# 07_Power_Supply_AC_to_DC.net
KiCad netlist of a schematic drawn in Altium Designer
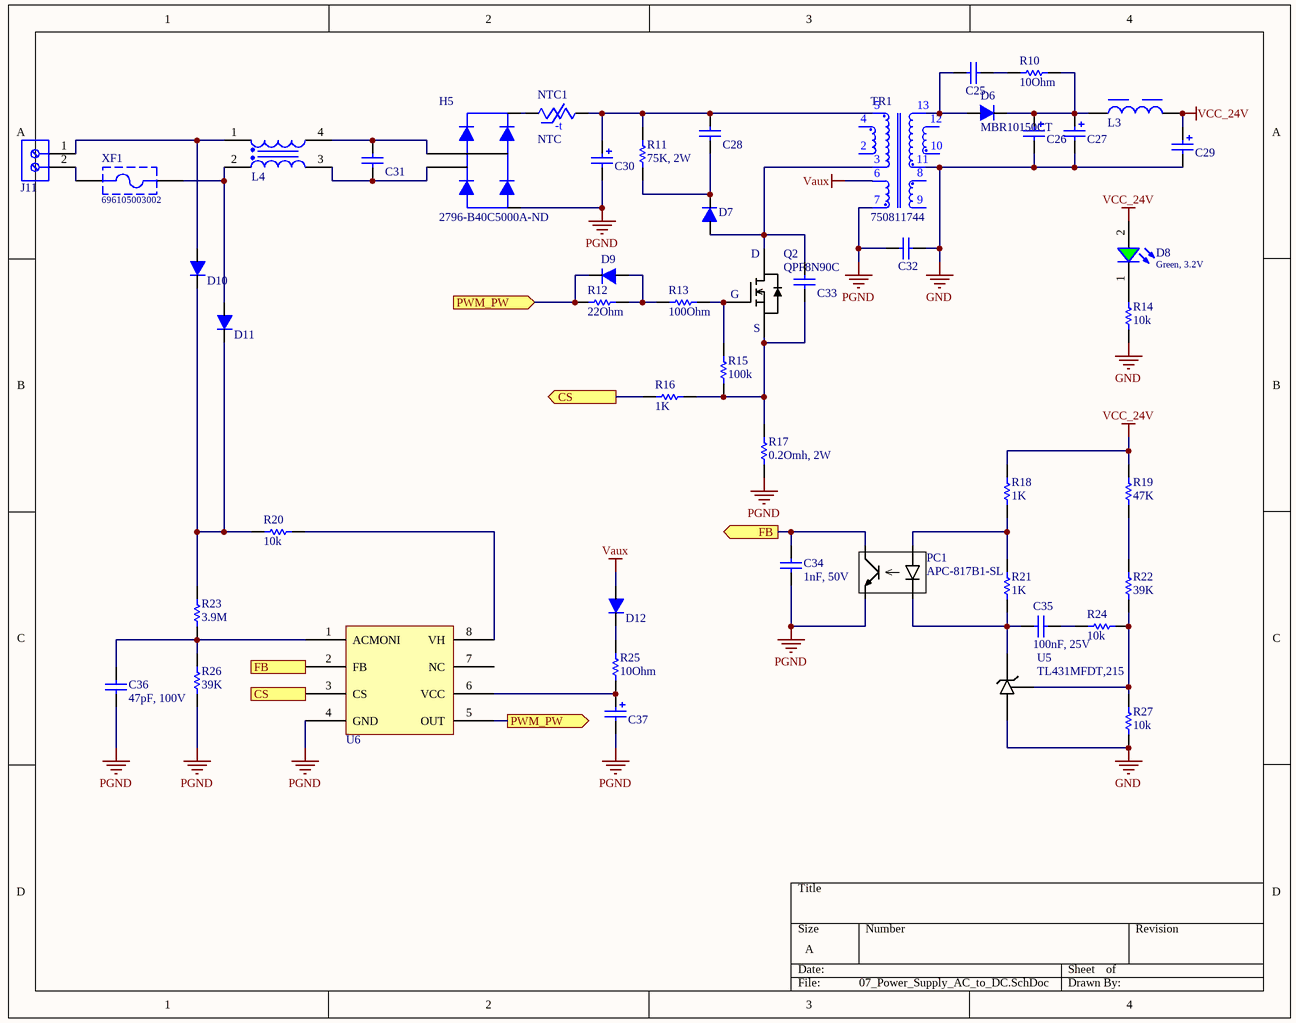
[diagram p0: 07_Power_Supply_AC_to_DC.SchDoc]

(export (version "E")
  (design (tool "Eeschema 10.0.6"))
  (components
    (comp (ref "C25")
      (value "1nF")
      (footprint "WCAP-CSMH_0805_L2W1.25H0.8_Reflow")
      (fields
        (field (name "MANUFACTURER PART NUMBER") "885342207013")
        (field (name "MANUFACTURER") "Wurth Elektronik")
      )
      (libsource (lib "Altium_WCAP-CSMH (rev22c)") (part "885342207013"))
    )
    (comp (ref "C26")
      (value "1200uF")
      (footprint "WCAP-ATG8_D16H31.5")
      (description "WCAP-ATG8 Aluminum Electrolytic Capacitor, Radial THT, D16xH31.5mm, 1200uF, 63V")
      (fields
        (field (name "MANUFACTURER") "Wurth Elektronik")
        (field (name "MANUFACTURER PART NUMBER") "860010780025")
      )
      (libsource (lib "Altium_WCAP-ATG8 (rev22a)") (part "860010780025"))
    )
    (comp (ref "C27")
      (value "1200uF")
      (footprint "WCAP-ATG8_D16H31.5")
      (description "WCAP-ATG8 Aluminum Electrolytic Capacitor, Radial THT, D16xH31.5mm, 1200uF, 63V")
      (fields
        (field (name "MANUFACTURER") "Wurth Elektronik")
        (field (name "MANUFACTURER PART NUMBER") "860010780025")
      )
      (libsource (lib "Altium_WCAP-ATG8 (rev22a)") (part "860010780025"))
    )
    (comp (ref "C28")
      (value "4.7nF")
      (footprint "WCAP-CSMH_1206_L3.2W1.6H1.25")
      (fields
        (field (name "MANUFACTURER PART NUMBER") "885342208008")
        (field (name "MANUFACTURER") "Wurth Elektronik")
      )
      (libsource (lib "Altium_WCAP-CSMH (rev22c)") (part "885342208008"))
    )
    (comp (ref "C29")
      (value "100uF")
      (footprint "WCAP-ATG8_D8H11.5")
      (description "WCAP-ATG8 Aluminum Electrolytic Capacitor, Radial THT, D8xH11.5mm, 100uF, 50V")
      (fields
        (field (name "MANUFACTURER") "Wurth Elektronik")
        (field (name "MANUFACTURER PART NUMBER") "860010674014")
      )
      (libsource (lib "Altium_WCAP-ATG8 (rev22a)") (part "860010674014"))
    )
    (comp (ref "C30")
      (value "220uF")
      (footprint "WCAP-AI3H_D22H50")
      (description "WCAP-AI3H Aluminum Electrolytic Capacitor, Snap-In, D22xH50mm, 220uF, 450V")
      (fields
        (field (name "MANUFACTURER") "Wurth Elektronik")
        (field (name "MANUFACTURER PART NUMBER") "861141483007")
      )
      (libsource (lib "Altium_WCAP-AI3H (rev22a)") (part "861141483007"))
    )
    (comp (ref "C31")
      (value "2.2uF")
      (footprint "WCAP-FTX2_L26W15H25")
      (description "WCAP-FTX2 Film Capacitor, THT, L26W15H25mm, 2.2uF, 275VAC")
      (fields
        (field (name "MANUFACTURER") "Wurth Elektronik")
        (field (name "MANUFACTURER PART NUMBER") "890324026034")
      )
      (libsource (lib "Altium_WCAP-FTX2 (rev22a)") (part "890324026034"))
    )
    (comp (ref "C32")
      (value "2.2nF")
      (footprint "WCAP-CSSA_2211_L5.7W2.8H2.5")
      (description "WCAP-CSSA Multilayer Ceramic Chip Safety Capacitor, 2211, X7R Class II, X1/Y2, 2.2nF, 250VAC")
      (fields
        (field (name "MANUFACTURER") "Wurth Elektronik")
        (field (name "MANUFACTURER PART NUMBER") "8853522130151")
      )
      (libsource (lib "Altium_WCAP-CSSA (rev22a)") (part "8853522130151"))
    )
    (comp (ref "C33")
      (value "22pF")
      (footprint "WCAP-CSMH_1210_L3.2W2.5H0.95")
      (fields
        (field (name "MANUFACTURER PART NUMBER") "885342009002")
        (field (name "MANUFACTURER") "Wurth Elektronik")
      )
      (libsource (lib "Altium_WCAP-CSMH (rev22c)") (part "885342009002"))
    )
    (comp (ref "C34")
      (value "1nF, 50V")
      (footprint "WCAP-CSGP_0805_H=0.8mm_Reflow")
      (description "WCAP-CSGP Multilayer Ceramic Chip Capacitor, General Purpose, size 0805, NP0, 1nF, 50V")
      (fields
        (field (name "MANUFACTURER PART NUMBER") "885012007063")
        (field (name "MANUFACTURER") "Wurth Elektronik")
      )
      (libsource (lib "Altium_WCAP-CSGP (rev20a)") (part "885012007063"))
    )
    (comp (ref "C35")
      (value "100nF, 25V")
      (footprint "WCAP-CSGP_0805_H=0.8mm_Reflow")
      (description "WCAP-CSGP Multilayer Ceramic Chip Capacitor, General Purpose, size 0805, X7R, 100nF, 25V")
      (fields
        (field (name "MANUFACTURER PART NUMBER") "885012207072")
        (field (name "MANUFACTURER") "Wurth Elektronik")
      )
      (libsource (lib "Altium_WCAP-CSGP (rev20a)") (part "885012207072"))
    )
    (comp (ref "C36")
      (value "47pF, 100V")
      (footprint "WCAP-CSGP_0805_H=0.6mm_Reflow")
      (description "WCAP-CSGP Multilayer Ceramic Chip Capacitor, General Purpose, size 0805, NP0, 47pF, 100V")
      (fields
        (field (name "MANUFACTURER PART NUMBER") "885012007080")
        (field (name "MANUFACTURER") "Wurth Elektronik")
      )
      (libsource (lib "Altium_WCAP-CSGP (rev20a)") (part "885012007080"))
    )
    (comp (ref "C37")
      (value "10uF")
      (footprint "WCAP-ATG8_D5H11")
      (description "WCAP-ATG8 Aluminum Electrolytic Capacitor, Radial THT, D5xH11mm, 10uF, 50V")
      (fields
        (field (name "MANUFACTURER") "Wurth Elektronik")
        (field (name "MANUFACTURER PART NUMBER") "860010672009")
      )
      (libsource (lib "Altium_WCAP-ATG8 (rev22a)") (part "860010672009"))
    )
    (comp (ref "D6")
      (value "MBR10150CT")
      (footprint "MBR10150CT")
      (description "DIODE ARRAY SCHOTTKY 150V TO220")
      (fields (field (name "MFR") "SMC Diode Solutions"))
      (libsource (lib "YenDoo") (part "Diode"))
    )
    (comp (ref "D7")
      (value "RS1M-13-F")
      (footprint "SMA")
      (description "DIODE GEN PURP 1KV 1A SMA")
      (fields (field (name "MFR") "Diodes Incorporated"))
      (libsource (lib "YenDoo") (part "Diode"))
    )
    (comp (ref "D8")
      (value "Green, 3.2V")
      (footprint "WL-SMCW_0603_H=0.7mm")
      (description "WL-SMCW SMT Mono-color Chip LED Waterclear, size 0603, Green, 3.2V, 140deg")
      (fields (field (name "PART NUMBER") "150060GS75000") (field (name "PUBLISHER") "Wurth Elektronik"))
      (libsource (lib "Altium_WL-SMCW (rev20a)") (part "150060GS75000"))
    )
    (comp (ref "D9")
      (value "CDBA360-HF")
      (footprint "SMA")
      (description "DIODE SCHOTTKY 60V 3A DO214AC")
      (fields (field (name "MFR") "Comchip Technology"))
      (libsource (lib "YenDoo") (part "Diode"))
    )
    (comp (ref "D10")
      (value "RFU02VSM8STR")
      (footprint "Flat Lead")
      (description "DIODE GP 800V 200MA TUMD2SM")
      (fields (field (name "MFR") "Rohm Semiconductor"))
      (libsource (lib "YenDoo") (part "Diode"))
    )
    (comp (ref "D11")
      (value "RFU02VSM8STR")
      (footprint "Flat Lead")
      (description "DIODE GP 800V 200MA TUMD2SM")
      (fields (field (name "MFR") "Rohm Semiconductor"))
      (libsource (lib "YenDoo") (part "Diode"))
    )
    (comp (ref "D12")
      (value "RS1M-13-F")
      (footprint "SMA")
      (description "DIODE GEN PURP 1KV 1A SMA")
      (fields (field (name "MFR") "Diodes Incorporated"))
      (libsource (lib "YenDoo") (part "Diode"))
    )
    (comp (ref "H5")
      (value "2796-B40C5000A-ND")
      (footprint "GBJ-4")
      (description "Bridge Rectifier Single Phase Standard 80 V Through Hole 4-SIP")
      (libsource (lib "YenDoo") (part "H Bridge"))
    )
    (comp (ref "J11")
      (value "691137710002")
      (footprint "691137710002")
      (description "WR-TBL Series 1377 Horizontal Entry, Through Hole, pitch 5mm, 2p")
      (fields (field (name "MANUFACTURER") "Wurth Elektronik"))
      (libsource (lib "Altium_WR-TBL (rev22a)") (part "691137710002"))
    )
    (comp (ref "L3")
      (value "10µH, 7A")
      (footprint "WE-LHMI_1040")
      (description "WE-LHMI SMT Power Inductor, size 1040, 10µH, 7A, 30mΩ")
      (fields
        (field (name "MANUFACTURER PART NUMBER") "74437368100")
        (field (name "MANUFACTURER") "Wurth Elektronik")
      )
      (libsource (lib "WE-LHMI (rev22a)") (part "74437368100"))
    )
    (comp (ref "L4")
      (value "13mH")
      (footprint "WE-FC_UT20V")
      (description "WE-FC THT Common Mode Power Line Choke, UT20V, 13mH, 0.8A, 0.708Ω")
      (fields
        (field (name "MANUFACTURER PART NUMBER") "7448640415")
        (field (name "MANUFACTURER") "Wurth Elektronik")
      )
      (libsource (lib "WE-FC (rev22a)") (part "7448640415"))
    )
    (comp (ref "NTC1")
      (value "NTC")
      (footprint "NTC")
      (description "THERMISTOR NTC 15OHM 3000K")
      (fields (field (name "MFR") "EPCOS - TDK Electronics") (field (name "TOLERANCE") "±20%"))
      (libsource (lib "YenDoo") (part "NTC"))
    )
    (comp (ref "PC1")
      (value "APC-817B1-SL")
      (footprint "APC-817B1-SL")
      (description "DIP4, DC INPUT, PHOTO TRANSISTOR")
      (fields (field (name "MFR") "American Bright Optoelectronics Corporation"))
      (libsource (lib "YenDoo") (part "Opto Isolator"))
    )
    (comp (ref "Q2")
      (value "QPF8N90C")
      (footprint "FQPF8N90C")
      (description "N-Channel 900 V 6.3A (Tc) 60W (Tc) Through Hole TO-220F-3")
      (fields (field (name "MFR") "onsemi"))
      (libsource (lib "YenDoo") (part "Mosfet"))
    )
    (comp (ref "R10")
      (value "10Ohm")
      (footprint "RES-SM-2512")
      (description "RES 10 OHM 0.5% 1W 2512")
      (fields (field (name "MFR") "KOA Speer Electronics, Inc.") (field (name "TOLERANCE") "±5%"))
      (libsource (lib "PIF_Library") (part "RESISTOR SMD"))
    )
    (comp (ref "R11")
      (value "75K, 2W")
      (footprint "RES-SM-2512")
      (description "RES SMD 75K OHM 1% 2W 2512")
      (fields (field (name "MFR") "TE Connectivity Passive Product") (field (name "TOLERANCE") "±1%"))
      (libsource (lib "PIF_Library") (part "RESISTOR SMD"))
    )
    (comp (ref "R12")
      (value "22Ohm")
      (footprint "RES-SM-0805")
      (description "RES 22 OHM 1% 1/4W 0805")
      (fields (field (name "MFR") "KOA Speer Electronics, Inc.") (field (name "TOLERANCE") "±1%"))
      (libsource (lib "PIF_Library") (part "RESISTOR SMD"))
    )
    (comp (ref "R13")
      (value "100Ohm")
      (footprint "RES-SM-0805")
      (description "RES 100 OHM 5% 1/4W 0805")
      (fields (field (name "MFR") "KOA Speer Electronics, Inc.") (field (name "TOLERANCE") "±5%"))
      (libsource (lib "PIF_Library") (part "RESISTOR SMD"))
    )
    (comp (ref "R14")
      (value "10k")
      (footprint "RES-SM-0805")
      (description "RES 10K OHM 1% 1/4W 0805")
      (fields (field (name "MFR") "KOA Speer Electronics, Inc.") (field (name "TOLERANCE") "±1%"))
      (libsource (lib "PIF_Library") (part "RESISTOR SMD"))
    )
    (comp (ref "R15")
      (value "100k")
      (footprint "RES-SM-0805")
      (description "RES 100K OHM 1% 1/4W 0805")
      (fields (field (name "MFR") "KOA Speer Electronics, Inc.") (field (name "TOLERANCE") "±1%"))
      (libsource (lib "PIF_Library") (part "RESISTOR SMD"))
    )
    (comp (ref "R16")
      (value "1K")
      (footprint "RES-SM-0805")
      (description "RES 1K OHM 5% 1/4W 0805")
      (fields (field (name "MFR") "KOA Speer Electronics, Inc.") (field (name "TOLERANCE") "±5%"))
      (libsource (lib "PIF_Library") (part "RESISTOR SMD"))
    )
    (comp (ref "R17")
      (value "0.2Omh, 2W")
      (footprint "RES-SM-2010")
      (description "RES 0.2 OHM 2.0 W 1% 2010 SMD")
      (fields (field (name "MFR") "Vishay Dale") (field (name "TOLERANCE") "±1%"))
      (libsource (lib "PIF_Library") (part "RESISTOR SMD"))
    )
    (comp (ref "R18")
      (value "1K")
      (footprint "RES-SM-0805")
      (description "RES 1K OHM 5% 1/4W 0805")
      (fields (field (name "MFR") "KOA Speer Electronics, Inc.") (field (name "TOLERANCE") "±5%"))
      (libsource (lib "PIF_Library") (part "RESISTOR SMD"))
    )
    (comp (ref "R19")
      (value "47K")
      (footprint "RES-SM-0805")
      (description "RES 47K OHM 5% 1/4W 0805")
      (fields (field (name "MFR") "KOA Speer Electronics, Inc.") (field (name "TOLERANCE") "±5%"))
      (libsource (lib "PIF_Library") (part "RESISTOR SMD"))
    )
    (comp (ref "R20")
      (value "10k")
      (footprint "RES-SM-0805")
      (description "RES 10K OHM 1% 1/4W 0805")
      (fields (field (name "MFR") "KOA Speer Electronics, Inc.") (field (name "TOLERANCE") "±1%"))
      (libsource (lib "PIF_Library") (part "RESISTOR SMD"))
    )
    (comp (ref "R21")
      (value "1K")
      (footprint "RES-SM-0805")
      (description "RES 1K OHM 5% 1/4W 0805")
      (fields (field (name "MFR") "KOA Speer Electronics, Inc.") (field (name "TOLERANCE") "±5%"))
      (libsource (lib "PIF_Library") (part "RESISTOR SMD"))
    )
    (comp (ref "R22")
      (value "39K")
      (footprint "RES-SM-0805")
      (description "RES 39K OHM 5% 1/4W 0805")
      (fields (field (name "MFR") "KOA Speer Electronics, Inc.") (field (name "TOLERANCE") "±5%"))
      (libsource (lib "PIF_Library") (part "RESISTOR SMD"))
    )
    (comp (ref "R23")
      (value "3.9M")
      (footprint "RES-SM-0805")
      (description "RES 3.9M OHM 5% 1/4W 0805")
      (fields (field (name "MFR") "KOA Speer Electronics, Inc.") (field (name "TOLERANCE") "±5%"))
      (libsource (lib "PIF_Library") (part "RESISTOR SMD"))
    )
    (comp (ref "R24")
      (value "10k")
      (footprint "RES-SM-0805")
      (description "RES 10K OHM 1% 1/4W 0805")
      (fields (field (name "MFR") "KOA Speer Electronics, Inc.") (field (name "TOLERANCE") "±1%"))
      (libsource (lib "PIF_Library") (part "RESISTOR SMD"))
    )
    (comp (ref "R25")
      (value "10Ohm")
      (footprint "RES-SM-0805")
      (description "RES 10 OHM 1% 1/4W 0805")
      (fields (field (name "MFR") "KOA Speer Electronics, Inc.") (field (name "TOLERANCE") "±1%"))
      (libsource (lib "PIF_Library") (part "RESISTOR SMD"))
    )
    (comp (ref "R26")
      (value "39K")
      (footprint "RES-SM-0805")
      (description "RES 39K OHM 5% 1/4W 0805")
      (fields (field (name "MFR") "KOA Speer Electronics, Inc.") (field (name "TOLERANCE") "±5%"))
      (libsource (lib "PIF_Library") (part "RESISTOR SMD"))
    )
    (comp (ref "R27")
      (value "10k")
      (footprint "RES-SM-0805")
      (description "RES 10K OHM 1% 1/4W 0805")
      (fields (field (name "MFR") "KOA Speer Electronics, Inc.") (field (name "TOLERANCE") "±1%"))
      (libsource (lib "PIF_Library") (part "RESISTOR SMD"))
    )
    (comp (ref "TR1")
      (value "750811744")
      (footprint "750811744")
      (description "Flyback Converters For For DC/DC Converters SMPS Transformer 4000Vrms Isolation 80kHz Through Hole")
      (fields (field (name "MFR") "Würth Elektronik"))
      (libsource (lib "YenDoo") (part "750811744"))
    )
    (comp (ref "U5")
      (value "TL431MFDT,215")
      (footprint "TO-236AB")
      (description "IC VREF SHUNT ADJ 2% TO236AB")
      (fields (field (name "MFR") "Nexperia USA Inc.") (field (name "TOLERANCE") "±2%"))
      (libsource (lib "YenDoo") (part "IC Shunt"))
    )
    (comp (ref "U6")
      (value "BM1P061FJ-E2")
      (footprint "SOP-J8")
      (description "IC OFFLINE SWITCH FLYBACK 8SOPJ")
      (fields (field (name "MFR") "Rohm Semiconductor"))
      (libsource (lib "YenDoo") (part "IC PWM"))
    )
    (comp (ref "XF1")
      (value "696105003002")
      (footprint "696105003002")
      (description "WR-FSH Fuseholder THT Blocks PCB Clip Cover")
      (fields (field (name "MANUFACTURER") "Wurth Elektronik"))
      (libsource (lib "Altium_WR-FSH (rev21a)") (part "696105003002"))
    )
  )
  (nets
    (net (code "1") (name "/CS") (class "Default")
      (node (ref "R16") (pin "2") (pinfunction "2_2") (pintype "passive"))
      (node (ref "U6") (pin "3") (pinfunction "CS_3") (pintype "passive"))
    )
    (net (code "2") (name "/FB") (class "Default")
      (node (ref "C34") (pin "2") (pinfunction "2_2") (pintype "passive"))
      (node (ref "PC1") (pin "4") (pinfunction "4_4") (pintype "passive"))
      (node (ref "U6") (pin "2") (pinfunction "FB_2") (pintype "passive"))
    )
    (net (code "3") (name "/PWM_PW") (class "Default")
      (node (ref "D9") (pin "2") (pinfunction "K_2") (pintype "passive"))
      (node (ref "R12") (pin "1") (pinfunction "1_1") (pintype "passive"))
      (node (ref "U6") (pin "5") (pinfunction "OUT_5") (pintype "passive"))
    )
    (net (code "4") (name "GND") (class "Default")
      (node (ref "C26") (pin "2") (pinfunction "N_2") (pintype "passive"))
      (node (ref "C27") (pin "2") (pinfunction "N_2") (pintype "passive"))
      (node (ref "C29") (pin "2") (pinfunction "N_2") (pintype "passive"))
      (node (ref "C32") (pin "1") (pinfunction "1_1") (pintype "passive"))
      (node (ref "R14") (pin "2") (pinfunction "2_2") (pintype "passive"))
      (node (ref "R27") (pin "2") (pinfunction "2_2") (pintype "passive"))
      (node (ref "TR1") (pin "11") (pinfunction "11_11") (pintype "passive"))
      (node (ref "U5") (pin "3") (pinfunction "3_3") (pintype "passive"))
    )
    (net (code "5") (name "Net-(C25-Pad2)") (class "Default")
      (node (ref "C25") (pin "2") (pinfunction "2_2") (pintype "passive"))
      (node (ref "R10") (pin "1") (pinfunction "1_1") (pintype "passive"))
    )
    (net (code "6") (name "Net-(C26-P)") (class "Default")
      (node (ref "C26") (pin "1") (pinfunction "P_1") (pintype "passive"))
      (node (ref "C27") (pin "1") (pinfunction "P_1") (pintype "passive"))
      (node (ref "D6") (pin "2") (pinfunction "K_2") (pintype "passive"))
      (node (ref "L3") (pin "1") (pinfunction "1_1") (pintype "passive"))
      (node (ref "R10") (pin "2") (pinfunction "2_2") (pintype "passive"))
    )
    (net (code "7") (name "Net-(C30-P)") (class "Default")
      (node (ref "C28") (pin "2") (pinfunction "2_2") (pintype "passive"))
      (node (ref "C30") (pin "1") (pinfunction "P_1") (pintype "passive"))
      (node (ref "NTC1") (pin "2") (pinfunction "2_2") (pintype "passive"))
      (node (ref "R11") (pin "2") (pinfunction "2_2") (pintype "passive"))
      (node (ref "TR1") (pin "5") (pinfunction "5_5") (pintype "passive"))
    )
    (net (code "8") (name "Net-(C31-Pad1)") (class "Default")
      (node (ref "C31") (pin "1") (pinfunction "1_1") (pintype "passive"))
      (node (ref "H5") (pin "3") (pinfunction "~_3") (pintype "passive"))
      (node (ref "L4") (pin "3") (pinfunction "3_3") (pintype "passive"))
    )
    (net (code "9") (name "Net-(C31-Pad2)") (class "Default")
      (node (ref "C31") (pin "2") (pinfunction "2_2") (pintype "passive"))
      (node (ref "H5") (pin "2") (pinfunction "~_2") (pintype "passive"))
      (node (ref "L4") (pin "4") (pinfunction "4_4") (pintype "passive"))
    )
    (net (code "10") (name "Net-(C35-Pad1)") (class "Default")
      (node (ref "C35") (pin "1") (pinfunction "1_1") (pintype "passive"))
      (node (ref "PC1") (pin "2") (pinfunction "2_2") (pintype "passive"))
      (node (ref "R21") (pin "2") (pinfunction "2_2") (pintype "passive"))
      (node (ref "U5") (pin "1") (pinfunction "1_1") (pintype "passive"))
    )
    (net (code "11") (name "Net-(C35-Pad2)") (class "Default")
      (node (ref "C35") (pin "2") (pinfunction "2_2") (pintype "passive"))
      (node (ref "R24") (pin "1") (pinfunction "1_1") (pintype "passive"))
    )
    (net (code "12") (name "Net-(C37-P)") (class "Default")
      (node (ref "C37") (pin "1") (pinfunction "P_1") (pintype "passive"))
      (node (ref "R25") (pin "1") (pinfunction "1_1") (pintype "passive"))
      (node (ref "U6") (pin "6") (pinfunction "VCC_6") (pintype "passive"))
    )
    (net (code "13") (name "Net-(D6-A)") (class "Default")
      (node (ref "C25") (pin "1") (pinfunction "1_1") (pintype "passive"))
      (node (ref "D6") (pin "1") (pinfunction "A_1") (pintype "passive"))
      (node (ref "TR1") (pin "13") (pinfunction "13_13") (pintype "passive"))
    )
    (net (code "14") (name "Net-(D7-A)") (class "Default")
      (node (ref "C33") (pin "2") (pinfunction "2_2") (pintype "passive"))
      (node (ref "D7") (pin "1") (pinfunction "A_1") (pintype "passive"))
      (node (ref "Q2") (pin "2") (pinfunction "D_2") (pintype "passive"))
      (node (ref "TR1") (pin "3") (pinfunction "3_3") (pintype "passive"))
    )
    (net (code "15") (name "Net-(D7-K)") (class "Default")
      (node (ref "C28") (pin "1") (pinfunction "1_1") (pintype "passive"))
      (node (ref "D7") (pin "2") (pinfunction "K_2") (pintype "passive"))
      (node (ref "R11") (pin "1") (pinfunction "1_1") (pintype "passive"))
    )
    (net (code "16") (name "Net-(D8-K)") (class "Default")
      (node (ref "D8") (pin "1") (pinfunction "K_1") (pintype "passive"))
      (node (ref "R14") (pin "1") (pinfunction "1_1") (pintype "passive"))
    )
    (net (code "17") (name "Net-(D9-A)") (class "Default")
      (node (ref "D9") (pin "1") (pinfunction "A_1") (pintype "passive"))
      (node (ref "R12") (pin "2") (pinfunction "2_2") (pintype "passive"))
      (node (ref "R13") (pin "1") (pinfunction "1_1") (pintype "passive"))
    )
    (net (code "18") (name "Net-(D10-A)") (class "Default")
      (node (ref "D10") (pin "1") (pinfunction "A_1") (pintype "passive"))
      (node (ref "J11") (pin "1") (pinfunction "1_1") (pintype "passive"))
      (node (ref "L4") (pin "1") (pinfunction "1_1") (pintype "passive"))
    )
    (net (code "19") (name "Net-(D10-K)") (class "Default")
      (node (ref "D10") (pin "2") (pinfunction "K_2") (pintype "passive"))
      (node (ref "D11") (pin "2") (pinfunction "K_2") (pintype "passive"))
      (node (ref "R20") (pin "2") (pinfunction "2_2") (pintype "passive"))
      (node (ref "R23") (pin "2") (pinfunction "2_2") (pintype "passive"))
    )
    (net (code "20") (name "Net-(D11-A)") (class "Default")
      (node (ref "D11") (pin "1") (pinfunction "A_1") (pintype "passive"))
      (node (ref "L4") (pin "2") (pinfunction "2_2") (pintype "passive"))
      (node (ref "XF1") (pin "2") (pinfunction "2_2") (pintype "passive"))
    )
    (net (code "21") (name "Net-(D12-K)") (class "Default")
      (node (ref "D12") (pin "2") (pinfunction "K_2") (pintype "passive"))
      (node (ref "R25") (pin "2") (pinfunction "2_2") (pintype "passive"))
    )
    (net (code "22") (name "Net-(H5-+)") (class "Default")
      (node (ref "H5") (pin "1") (pinfunction "+_1") (pintype "passive"))
      (node (ref "NTC1") (pin "1") (pinfunction "1_1") (pintype "passive"))
    )
    (net (code "23") (name "Net-(J11-Pad2)") (class "Default")
      (node (ref "J11") (pin "2") (pinfunction "2_2") (pintype "passive"))
      (node (ref "XF1") (pin "1") (pinfunction "1_1") (pintype "passive"))
    )
    (net (code "24") (name "Net-(PC1-Pad1)") (class "Default")
      (node (ref "PC1") (pin "1") (pinfunction "1_1") (pintype "passive"))
      (node (ref "R18") (pin "2") (pinfunction "2_2") (pintype "passive"))
      (node (ref "R21") (pin "1") (pinfunction "1_1") (pintype "passive"))
    )
    (net (code "25") (name "Net-(Q2-G)") (class "Default")
      (node (ref "Q2") (pin "1") (pinfunction "G_1") (pintype "passive"))
      (node (ref "R13") (pin "2") (pinfunction "2_2") (pintype "passive"))
      (node (ref "R15") (pin "2") (pinfunction "2_2") (pintype "passive"))
    )
    (net (code "26") (name "Net-(Q2-S)") (class "Default")
      (node (ref "C33") (pin "1") (pinfunction "1_1") (pintype "passive"))
      (node (ref "Q2") (pin "3") (pinfunction "S_3") (pintype "passive"))
      (node (ref "R15") (pin "1") (pinfunction "1_1") (pintype "passive"))
      (node (ref "R16") (pin "1") (pinfunction "1_1") (pintype "passive"))
      (node (ref "R17") (pin "2") (pinfunction "2_2") (pintype "passive"))
    )
    (net (code "27") (name "Net-(R19-Pad1)") (class "Default")
      (node (ref "R19") (pin "1") (pinfunction "1_1") (pintype "passive"))
      (node (ref "R22") (pin "2") (pinfunction "2_2") (pintype "passive"))
    )
    (net (code "28") (name "Net-(R22-Pad1)") (class "Default")
      (node (ref "R22") (pin "1") (pinfunction "1_1") (pintype "passive"))
      (node (ref "R24") (pin "2") (pinfunction "2_2") (pintype "passive"))
      (node (ref "R27") (pin "1") (pinfunction "1_1") (pintype "passive"))
      (node (ref "U5") (pin "2") (pinfunction "2_2") (pintype "passive"))
    )
    (net (code "29") (name "Net-(U6-ACMONI)") (class "Default")
      (node (ref "C36") (pin "2") (pinfunction "2_2") (pintype "passive"))
      (node (ref "R23") (pin "1") (pinfunction "1_1") (pintype "passive"))
      (node (ref "R26") (pin "2") (pinfunction "2_2") (pintype "passive"))
      (node (ref "U6") (pin "1") (pinfunction "ACMONI_1") (pintype "passive"))
    )
    (net (code "30") (name "Net-(U6-VH)") (class "Default")
      (node (ref "R20") (pin "1") (pinfunction "1_1") (pintype "passive"))
      (node (ref "U6") (pin "8") (pinfunction "VH_8") (pintype "passive"))
    )
    (net (code "31") (name "PGND") (class "Default")
      (node (ref "C30") (pin "2") (pinfunction "N_2") (pintype "passive"))
      (node (ref "C32") (pin "2") (pinfunction "2_2") (pintype "passive"))
      (node (ref "C34") (pin "1") (pinfunction "1_1") (pintype "passive"))
      (node (ref "C36") (pin "1") (pinfunction "1_1") (pintype "passive"))
      (node (ref "C37") (pin "2") (pinfunction "N_2") (pintype "passive"))
      (node (ref "H5") (pin "4") (pinfunction "-_4") (pintype "passive"))
      (node (ref "PC1") (pin "3") (pinfunction "3_3") (pintype "passive"))
      (node (ref "R17") (pin "1") (pinfunction "1_1") (pintype "passive"))
      (node (ref "R26") (pin "1") (pinfunction "1_1") (pintype "passive"))
      (node (ref "TR1") (pin "7") (pinfunction "7_7") (pintype "passive"))
      (node (ref "U6") (pin "4") (pinfunction "GND_4") (pintype "passive"))
    )
    (net (code "32") (name "VCC_24V") (class "Default")
      (node (ref "C29") (pin "1") (pinfunction "P_1") (pintype "passive"))
      (node (ref "D8") (pin "2") (pinfunction "A_2") (pintype "passive"))
      (node (ref "L3") (pin "2") (pinfunction "2_2") (pintype "passive"))
      (node (ref "R18") (pin "1") (pinfunction "1_1") (pintype "passive"))
      (node (ref "R19") (pin "2") (pinfunction "2_2") (pintype "passive"))
    )
    (net (code "33") (name "Vaux") (class "Default")
      (node (ref "D12") (pin "1") (pinfunction "A_1") (pintype "passive"))
      (node (ref "TR1") (pin "6") (pinfunction "6_6") (pintype "passive"))
    )
    (net (code "34") (name "unconnected-(TR1-Pad2)") (class "Default")
      (node (ref "TR1") (pin "2") (pinfunction "2_2") (pintype "passive"))
    )
    (net (code "35") (name "unconnected-(TR1-Pad4)") (class "Default")
      (node (ref "TR1") (pin "4") (pinfunction "4_4") (pintype "passive"))
    )
    (net (code "36") (name "unconnected-(TR1-Pad8)") (class "Default")
      (node (ref "TR1") (pin "8") (pinfunction "8_8") (pintype "passive"))
    )
    (net (code "37") (name "unconnected-(TR1-Pad9)") (class "Default")
      (node (ref "TR1") (pin "9") (pinfunction "9_9") (pintype "passive"))
    )
    (net (code "38") (name "unconnected-(TR1-Pad10)") (class "Default")
      (node (ref "TR1") (pin "10") (pinfunction "10_10") (pintype "passive"))
    )
    (net (code "39") (name "unconnected-(TR1-Pad12)") (class "Default")
      (node (ref "TR1") (pin "12") (pinfunction "12_12") (pintype "passive"))
    )
    (net (code "40") (name "unconnected-(U6-NC-Pad7)") (class "Default")
      (node (ref "U6") (pin "7") (pinfunction "NC_7") (pintype "passive"))
    )
  )
)
